# warps_v30.net
KiCad netlist of a schematic drawn in EAGLE
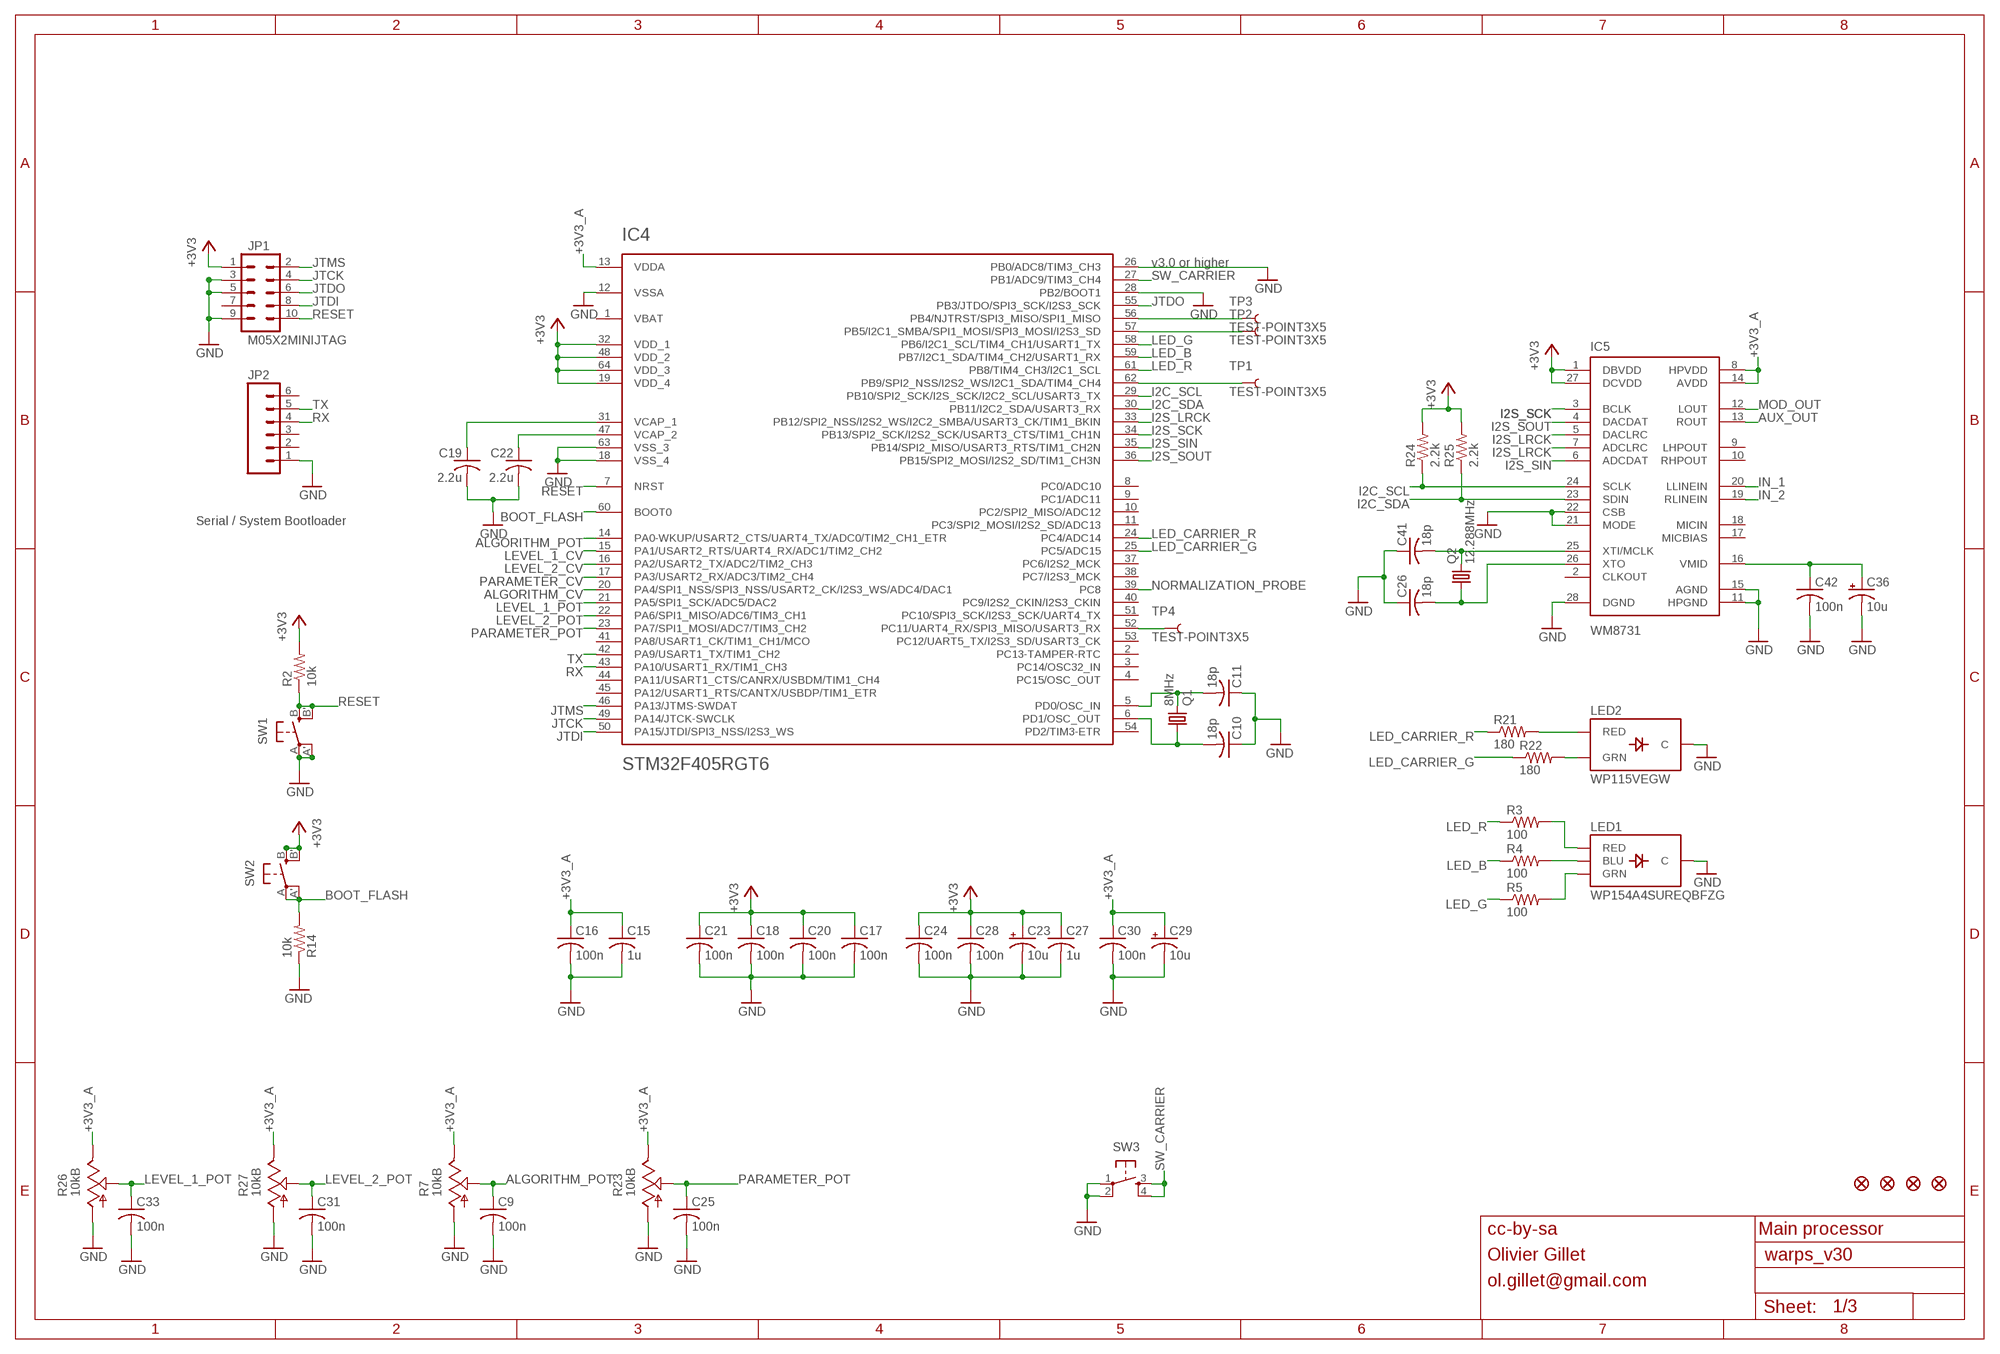
[diagram p0: schematic, sheet 1]
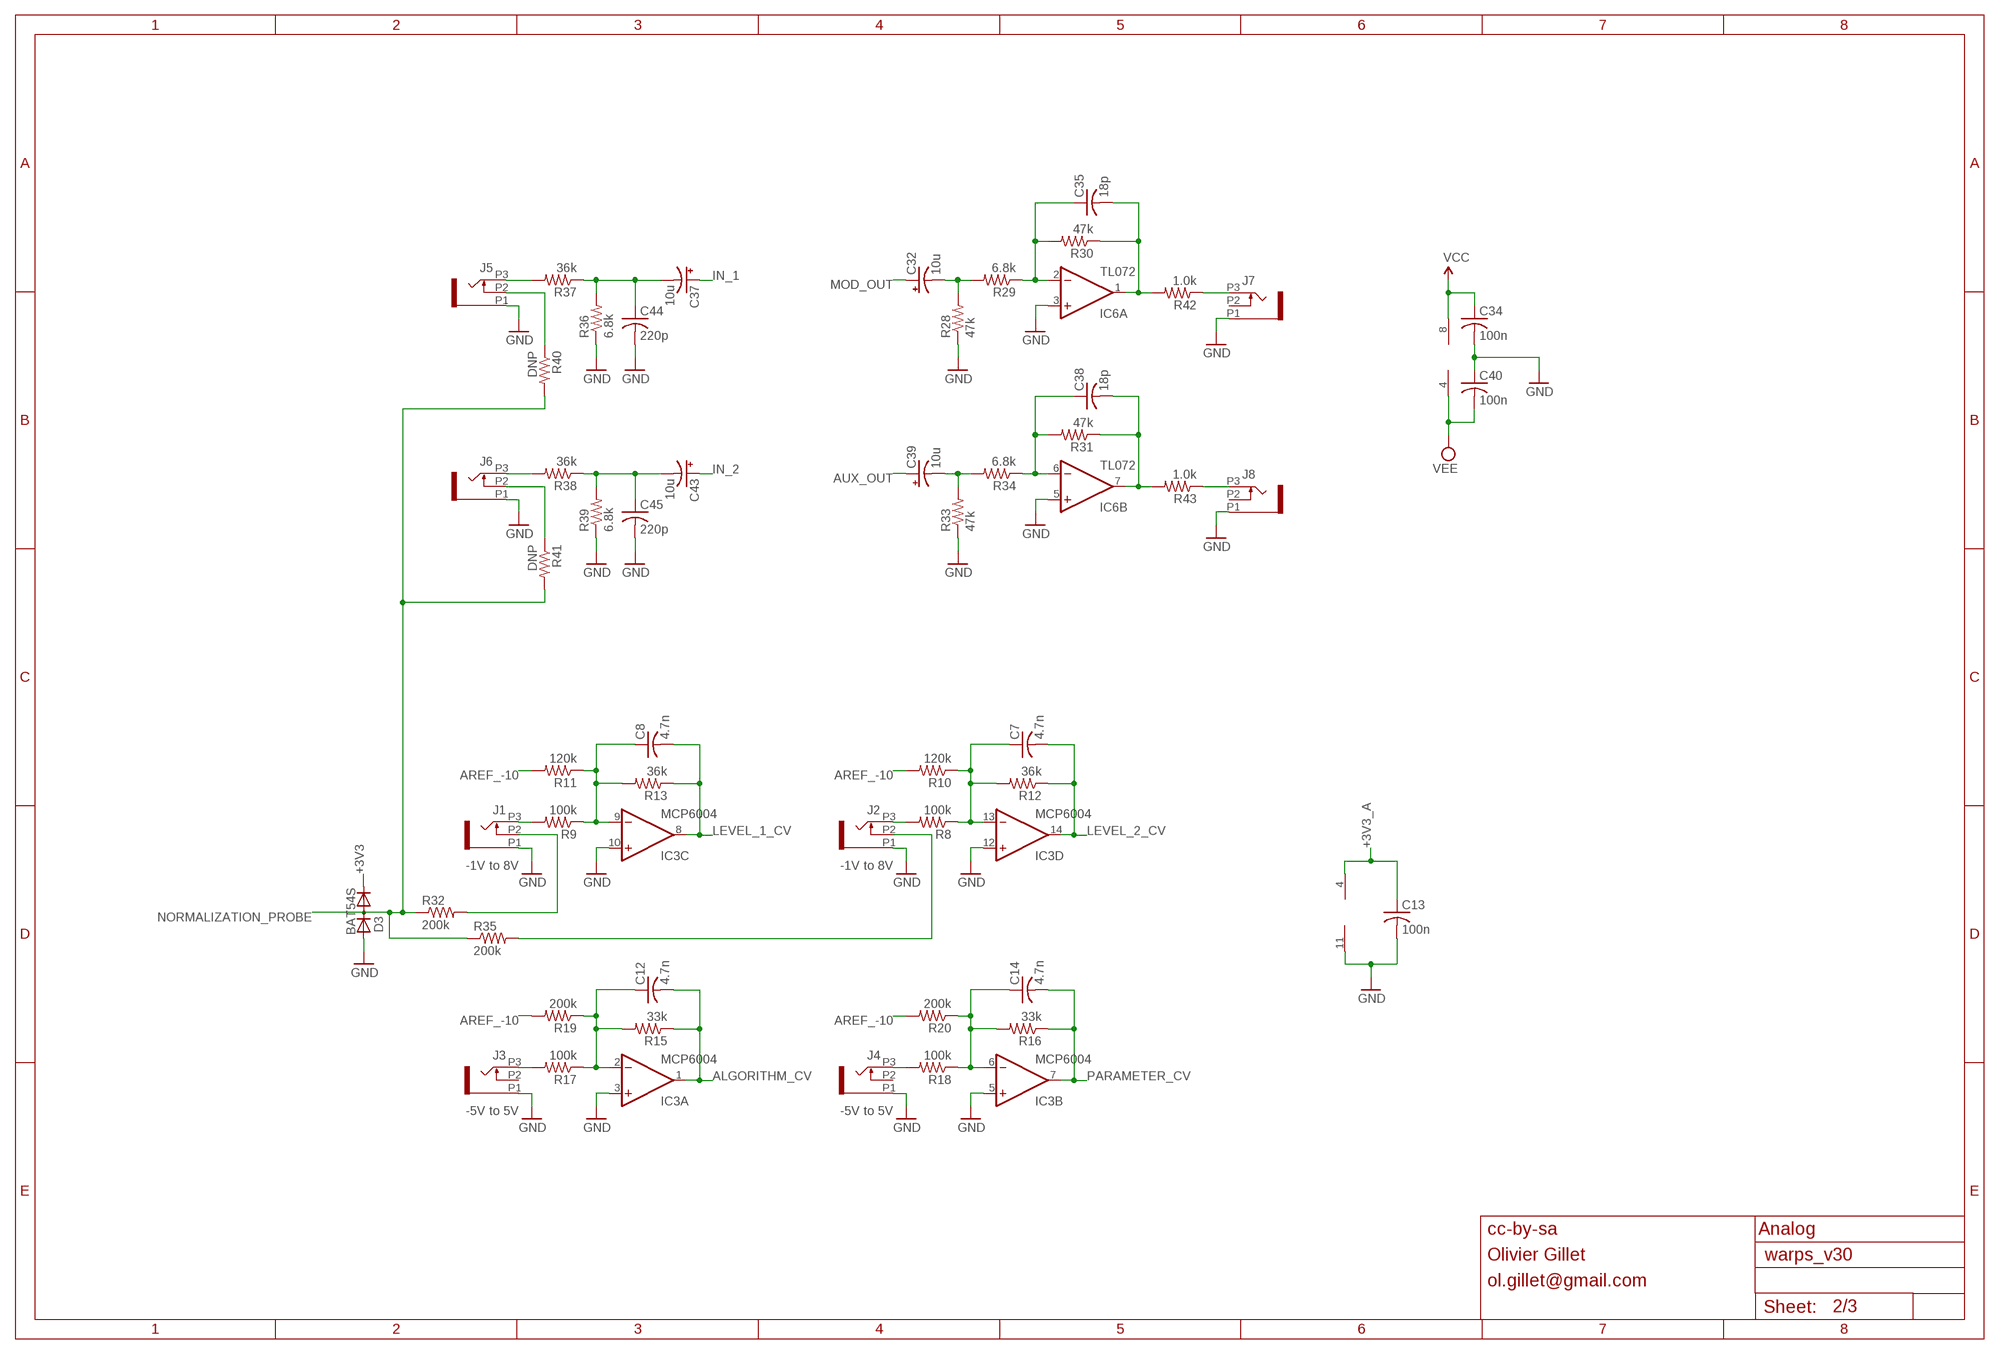
[diagram p1: schematic, sheet 2]
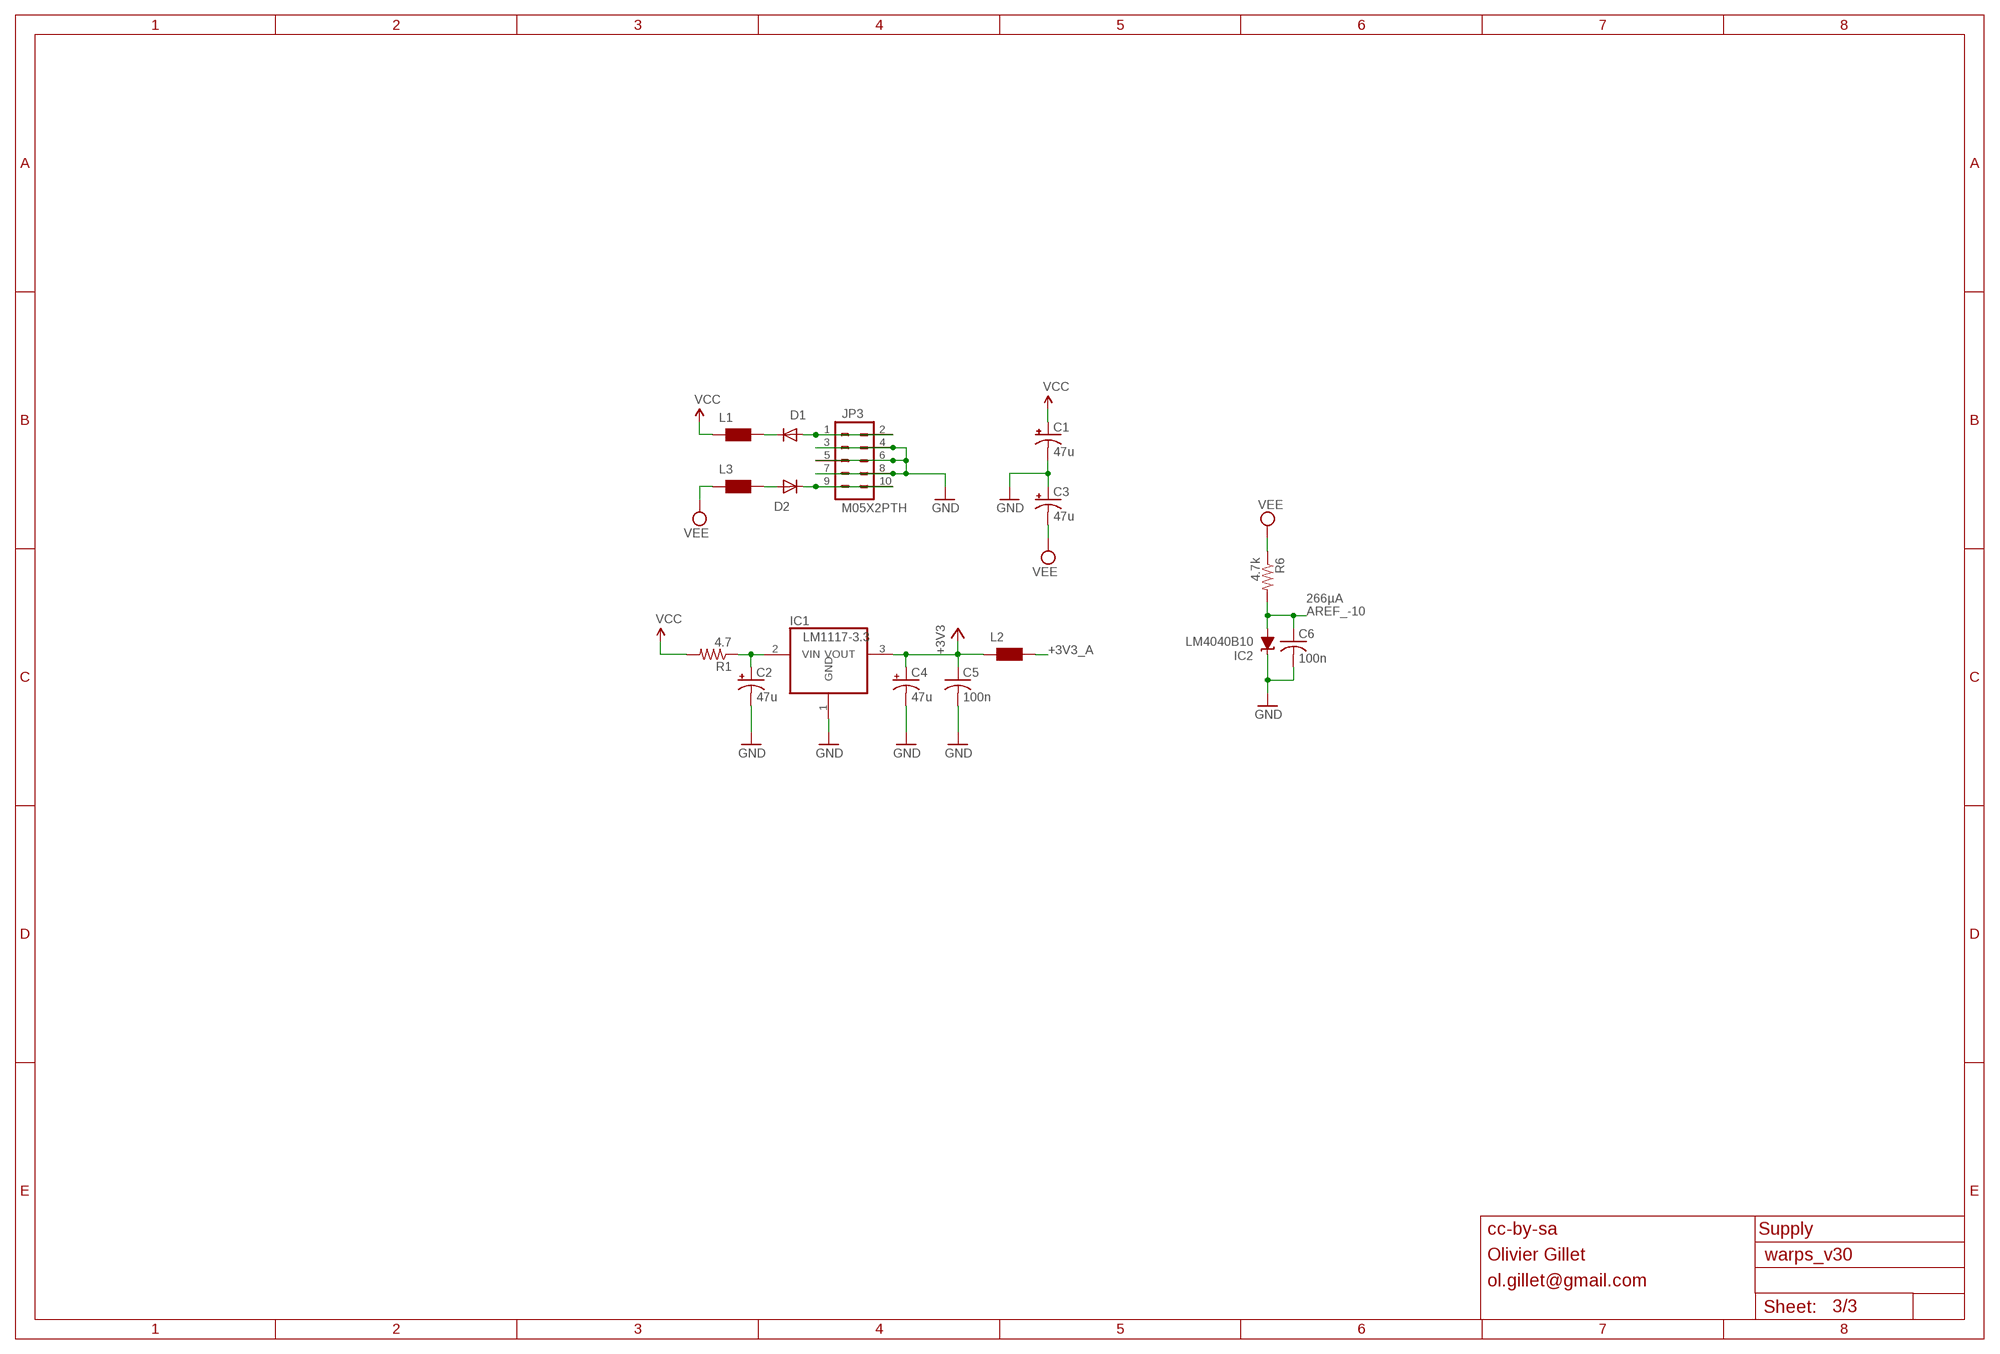
[diagram p2: schematic, sheet 3]

(export (version "E")
  (design (tool "Eeschema 10.0.6"))
  (components
    (comp (ref "C7")
      (value "4.7n")
      (footprint "eagle-import:C0603")
      (libsource (lib "eagle-import") (part "C-USC0603"))
    )
    (comp (ref "C8")
      (value "4.7n")
      (footprint "eagle-import:C0603")
      (libsource (lib "eagle-import") (part "C-USC0603"))
    )
    (comp (ref "C12")
      (value "4.7n")
      (footprint "eagle-import:C0603")
      (libsource (lib "eagle-import") (part "C-USC0603"))
    )
    (comp (ref "C13")
      (value "100n")
      (footprint "eagle-import:C0603")
      (libsource (lib "eagle-import") (part "C-USC0603"))
    )
    (comp (ref "C14")
      (value "4.7n")
      (footprint "eagle-import:C0603")
      (libsource (lib "eagle-import") (part "C-USC0603"))
    )
    (comp (ref "C32")
      (value "10u")
      (footprint "eagle-import:PANASONIC_A")
      (libsource (lib "eagle-import") (part "CPOL-USA"))
    )
    (comp (ref "C34")
      (value "100n")
      (footprint "eagle-import:C0603")
      (libsource (lib "eagle-import") (part "C-USC0603"))
    )
    (comp (ref "C35")
      (value "18p")
      (footprint "eagle-import:C0603")
      (libsource (lib "eagle-import") (part "C-USC0603"))
    )
    (comp (ref "C37")
      (value "10u")
      (footprint "eagle-import:PANASONIC_A")
      (libsource (lib "eagle-import") (part "CPOL-USA"))
    )
    (comp (ref "C38")
      (value "18p")
      (footprint "eagle-import:C0603")
      (libsource (lib "eagle-import") (part "C-USC0603"))
    )
    (comp (ref "C39")
      (value "10u")
      (footprint "eagle-import:PANASONIC_A")
      (libsource (lib "eagle-import") (part "CPOL-USA"))
    )
    (comp (ref "C40")
      (value "100n")
      (footprint "eagle-import:C0603")
      (libsource (lib "eagle-import") (part "C-USC0603"))
    )
    (comp (ref "C43")
      (value "10u")
      (footprint "eagle-import:PANASONIC_A")
      (libsource (lib "eagle-import") (part "CPOL-USA"))
    )
    (comp (ref "C44")
      (value "220p")
      (footprint "eagle-import:C0603")
      (libsource (lib "eagle-import") (part "C-USC0603"))
    )
    (comp (ref "C45")
      (value "220p")
      (footprint "eagle-import:C0603")
      (libsource (lib "eagle-import") (part "C-USC0603"))
    )
    (comp (ref "D3")
      (value "BAT54S")
      (footprint "eagle-import:SOT23")
      (libsource (lib "eagle-import") (part "DIODE_2CACA-SOT23"))
    )
    (comp (ref "IC3")
      (value "MCP6004")
      (footprint "eagle-import:SO14")
      (libsource (lib "eagle-import") (part "TL074D"))
    )
    (comp (ref "IC6")
      (value "TL072")
      (footprint "eagle-import:SO08")
      (libsource (lib "eagle-import") (part "TL072D"))
    )
    (comp (ref "J1")
      (value "PJ301_THONKICONN6")
      (footprint "eagle-import:WQP_PJ_301M6")
      (libsource (lib "eagle-import") (part "PJ301_THONKICONN6"))
    )
    (comp (ref "J2")
      (value "PJ301_THONKICONN6")
      (footprint "eagle-import:WQP_PJ_301M6")
      (libsource (lib "eagle-import") (part "PJ301_THONKICONN6"))
    )
    (comp (ref "J3")
      (value "PJ301_THONKICONN6")
      (footprint "eagle-import:WQP_PJ_301M6")
      (libsource (lib "eagle-import") (part "PJ301_THONKICONN6"))
    )
    (comp (ref "J4")
      (value "PJ301_THONKICONN6")
      (footprint "eagle-import:WQP_PJ_301M6")
      (libsource (lib "eagle-import") (part "PJ301_THONKICONN6"))
    )
    (comp (ref "J5")
      (value "PJ301_THONKICONN6")
      (footprint "eagle-import:WQP_PJ_301M6")
      (libsource (lib "eagle-import") (part "PJ301_THONKICONN6"))
    )
    (comp (ref "J6")
      (value "PJ301_THONKICONN6")
      (footprint "eagle-import:WQP_PJ_301M6")
      (libsource (lib "eagle-import") (part "PJ301_THONKICONN6"))
    )
    (comp (ref "J7")
      (value "PJ301_THONKICONN6")
      (footprint "eagle-import:WQP_PJ_301M6")
      (libsource (lib "eagle-import") (part "PJ301_THONKICONN6"))
    )
    (comp (ref "J8")
      (value "PJ301_THONKICONN6")
      (footprint "eagle-import:WQP_PJ_301M6")
      (libsource (lib "eagle-import") (part "PJ301_THONKICONN6"))
    )
    (comp (ref "R8")
      (value "100k")
      (footprint "eagle-import:R0603")
      (libsource (lib "eagle-import") (part "R-US_R0603"))
    )
    (comp (ref "R9")
      (value "100k")
      (footprint "eagle-import:R0603")
      (libsource (lib "eagle-import") (part "R-US_R0603"))
    )
    (comp (ref "R10")
      (value "120k")
      (footprint "eagle-import:R0603")
      (libsource (lib "eagle-import") (part "R-US_R0603"))
    )
    (comp (ref "R11")
      (value "120k")
      (footprint "eagle-import:R0603")
      (libsource (lib "eagle-import") (part "R-US_R0603"))
    )
    (comp (ref "R12")
      (value "36k")
      (footprint "eagle-import:R0603")
      (libsource (lib "eagle-import") (part "R-US_R0603"))
    )
    (comp (ref "R13")
      (value "36k")
      (footprint "eagle-import:R0603")
      (libsource (lib "eagle-import") (part "R-US_R0603"))
    )
    (comp (ref "R15")
      (value "33k")
      (footprint "eagle-import:R0603")
      (libsource (lib "eagle-import") (part "R-US_R0603"))
    )
    (comp (ref "R16")
      (value "33k")
      (footprint "eagle-import:R0603")
      (libsource (lib "eagle-import") (part "R-US_R0603"))
    )
    (comp (ref "R17")
      (value "100k")
      (footprint "eagle-import:R0603")
      (libsource (lib "eagle-import") (part "R-US_R0603"))
    )
    (comp (ref "R18")
      (value "100k")
      (footprint "eagle-import:R0603")
      (libsource (lib "eagle-import") (part "R-US_R0603"))
    )
    (comp (ref "R19")
      (value "200k")
      (footprint "eagle-import:R0603")
      (libsource (lib "eagle-import") (part "R-US_R0603"))
    )
    (comp (ref "R20")
      (value "200k")
      (footprint "eagle-import:R0603")
      (libsource (lib "eagle-import") (part "R-US_R0603"))
    )
    (comp (ref "R28")
      (value "47k")
      (footprint "eagle-import:R0603")
      (libsource (lib "eagle-import") (part "R-US_R0603"))
    )
    (comp (ref "R29")
      (value "6.8k")
      (footprint "eagle-import:R0603")
      (libsource (lib "eagle-import") (part "R-US_R0603"))
    )
    (comp (ref "R30")
      (value "47k")
      (footprint "eagle-import:R0603")
      (libsource (lib "eagle-import") (part "R-US_R0603"))
    )
    (comp (ref "R31")
      (value "47k")
      (footprint "eagle-import:R0603")
      (libsource (lib "eagle-import") (part "R-US_R0603"))
    )
    (comp (ref "R32")
      (value "200k")
      (footprint "eagle-import:R0603")
      (libsource (lib "eagle-import") (part "R-US_R0603"))
    )
    (comp (ref "R33")
      (value "47k")
      (footprint "eagle-import:R0603")
      (libsource (lib "eagle-import") (part "R-US_R0603"))
    )
    (comp (ref "R34")
      (value "6.8k")
      (footprint "eagle-import:R0603")
      (libsource (lib "eagle-import") (part "R-US_R0603"))
    )
    (comp (ref "R35")
      (value "200k")
      (footprint "eagle-import:R0603")
      (libsource (lib "eagle-import") (part "R-US_R0603"))
    )
    (comp (ref "R36")
      (value "6.8k")
      (footprint "eagle-import:R0603")
      (libsource (lib "eagle-import") (part "R-US_R0603"))
    )
    (comp (ref "R37")
      (value "36k")
      (footprint "eagle-import:R0603")
      (libsource (lib "eagle-import") (part "R-US_R0603"))
    )
    (comp (ref "R38")
      (value "36k")
      (footprint "eagle-import:R0603")
      (libsource (lib "eagle-import") (part "R-US_R0603"))
    )
    (comp (ref "R39")
      (value "6.8k")
      (footprint "eagle-import:R0603")
      (libsource (lib "eagle-import") (part "R-US_R0603"))
    )
    (comp (ref "R40")
      (value "DNP")
      (footprint "eagle-import:R0603")
      (libsource (lib "eagle-import") (part "R-US_R0603"))
    )
    (comp (ref "R41")
      (value "DNP")
      (footprint "eagle-import:R0603")
      (libsource (lib "eagle-import") (part "R-US_R0603"))
    )
    (comp (ref "R42")
      (value "1.0k")
      (footprint "eagle-import:R0603")
      (libsource (lib "eagle-import") (part "R-US_R0603"))
    )
    (comp (ref "R43")
      (value "1.0k")
      (footprint "eagle-import:R0603")
      (libsource (lib "eagle-import") (part "R-US_R0603"))
    )
    (comp (ref "C9")
      (value "100n")
      (footprint "eagle-import:C0603")
      (libsource (lib "eagle-import") (part "C-USC0603"))
    )
    (comp (ref "C10")
      (value "18p")
      (footprint "eagle-import:C0603")
      (libsource (lib "eagle-import") (part "C-USC0603"))
    )
    (comp (ref "C11")
      (value "18p")
      (footprint "eagle-import:C0603")
      (libsource (lib "eagle-import") (part "C-USC0603"))
    )
    (comp (ref "C15")
      (value "1u")
      (footprint "eagle-import:C0603")
      (libsource (lib "eagle-import") (part "C-USC0603"))
    )
    (comp (ref "C16")
      (value "100n")
      (footprint "eagle-import:C0603")
      (libsource (lib "eagle-import") (part "C-USC0603"))
    )
    (comp (ref "C17")
      (value "100n")
      (footprint "eagle-import:C0603")
      (libsource (lib "eagle-import") (part "C-USC0603"))
    )
    (comp (ref "C18")
      (value "100n")
      (footprint "eagle-import:C0603")
      (libsource (lib "eagle-import") (part "C-USC0603"))
    )
    (comp (ref "C19")
      (value "2.2u")
      (footprint "eagle-import:C0805")
      (libsource (lib "eagle-import") (part "C-USC0805"))
    )
    (comp (ref "C20")
      (value "100n")
      (footprint "eagle-import:C0603")
      (libsource (lib "eagle-import") (part "C-USC0603"))
    )
    (comp (ref "C21")
      (value "100n")
      (footprint "eagle-import:C0603")
      (libsource (lib "eagle-import") (part "C-USC0603"))
    )
    (comp (ref "C22")
      (value "2.2u")
      (footprint "eagle-import:C0805")
      (libsource (lib "eagle-import") (part "C-USC0805"))
    )
    (comp (ref "C23")
      (value "10u")
      (footprint "eagle-import:PANASONIC_A")
      (libsource (lib "eagle-import") (part "CPOL-USA"))
    )
    (comp (ref "C24")
      (value "100n")
      (footprint "eagle-import:C0603")
      (libsource (lib "eagle-import") (part "C-USC0603"))
    )
    (comp (ref "C25")
      (value "100n")
      (footprint "eagle-import:C0603")
      (libsource (lib "eagle-import") (part "C-USC0603"))
    )
    (comp (ref "C26")
      (value "18p")
      (footprint "eagle-import:C0603")
      (libsource (lib "eagle-import") (part "C-USC0603"))
    )
    (comp (ref "C27")
      (value "1u")
      (footprint "eagle-import:C0603")
      (libsource (lib "eagle-import") (part "C-USC0603"))
    )
    (comp (ref "C28")
      (value "100n")
      (footprint "eagle-import:C0603")
      (libsource (lib "eagle-import") (part "C-USC0603"))
    )
    (comp (ref "C29")
      (value "10u")
      (footprint "eagle-import:PANASONIC_A")
      (libsource (lib "eagle-import") (part "CPOL-USA"))
    )
    (comp (ref "C30")
      (value "100n")
      (footprint "eagle-import:C0603")
      (libsource (lib "eagle-import") (part "C-USC0603"))
    )
    (comp (ref "C31")
      (value "100n")
      (footprint "eagle-import:C0603")
      (libsource (lib "eagle-import") (part "C-USC0603"))
    )
    (comp (ref "C33")
      (value "100n")
      (footprint "eagle-import:C0603")
      (libsource (lib "eagle-import") (part "C-USC0603"))
    )
    (comp (ref "C36")
      (value "10u")
      (footprint "eagle-import:PANASONIC_A")
      (libsource (lib "eagle-import") (part "CPOL-USA"))
    )
    (comp (ref "C41")
      (value "18p")
      (footprint "eagle-import:C0603")
      (libsource (lib "eagle-import") (part "C-USC0603"))
    )
    (comp (ref "C42")
      (value "100n")
      (footprint "eagle-import:C0603")
      (libsource (lib "eagle-import") (part "C-USC0603"))
    )
    (comp (ref "F1")
      (value "FIDUCIAL1X2")
      (footprint "eagle-import:FIDUCIAL-1X2")
      (libsource (lib "eagle-import") (part "FIDUCIAL1X2"))
    )
    (comp (ref "F2")
      (value "FIDUCIAL1X2")
      (footprint "eagle-import:FIDUCIAL-1X2")
      (libsource (lib "eagle-import") (part "FIDUCIAL1X2"))
    )
    (comp (ref "F3")
      (value "FIDUCIAL1X2")
      (footprint "eagle-import:FIDUCIAL-1X2")
      (libsource (lib "eagle-import") (part "FIDUCIAL1X2"))
    )
    (comp (ref "F4")
      (value "FIDUCIAL1X2")
      (footprint "eagle-import:FIDUCIAL-1X2")
      (libsource (lib "eagle-import") (part "FIDUCIAL1X2"))
    )
    (comp (ref "IC4")
      (value "STM32F405RGT6")
      (footprint "eagle-import:TQFP-10X10-64")
      (libsource (lib "eagle-import") (part "STM32F20X"))
    )
    (comp (ref "IC5")
      (value "WM8731")
      (footprint "eagle-import:SSOP28")
      (libsource (lib "eagle-import") (part "WM8731"))
    )
    (comp (ref "JP1")
      (value "M05X2MINIJTAG")
      (footprint "eagle-import:2X5-1.27")
      (libsource (lib "eagle-import") (part "M05X2MINIJTAG"))
    )
    (comp (ref "JP2")
      (value "M06SIP")
      (footprint "eagle-import:1X06")
      (libsource (lib "eagle-import") (part "M06SIP"))
    )
    (comp (ref "LED1")
      (value "WP154A4SUREQBFZG")
      (footprint "eagle-import:LED-TRICOLOR-THROUGHHOLE")
      (libsource (lib "eagle-import") (part "LED-TRICOLOR-THROUGHHOLE"))
    )
    (comp (ref "LED2")
      (value "WP115VEGW")
      (footprint "eagle-import:LED-BICOLOR-THROUGHHOLE")
      (libsource (lib "eagle-import") (part "LED-BICOLOR-THROUGHHOLE"))
    )
    (comp (ref "Q1")
      (value "8MHz")
      (footprint "eagle-import:HC49UP")
      (libsource (lib "eagle-import") (part "CRYSTALHC49UP"))
    )
    (comp (ref "Q2")
      (value "12.288MHz")
      (footprint "eagle-import:HC49UP")
      (libsource (lib "eagle-import") (part "CRYSTALHC49UP"))
    )
    (comp (ref "R2")
      (value "10k")
      (footprint "eagle-import:R0603")
      (libsource (lib "eagle-import") (part "R-US_R0603"))
    )
    (comp (ref "R3")
      (value "100")
      (footprint "eagle-import:R0603")
      (libsource (lib "eagle-import") (part "R-US_R0603"))
    )
    (comp (ref "R4")
      (value "100")
      (footprint "eagle-import:R0603")
      (libsource (lib "eagle-import") (part "R-US_R0603"))
    )
    (comp (ref "R5")
      (value "100")
      (footprint "eagle-import:R0603")
      (libsource (lib "eagle-import") (part "R-US_R0603"))
    )
    (comp (ref "R7")
      (value "10kB")
      (footprint "eagle-import:ALPS_POT_VERTICAL_PS")
      (libsource (lib "eagle-import") (part "POT_USVERTICAL_PS"))
    )
    (comp (ref "R14")
      (value "10k")
      (footprint "eagle-import:R0603")
      (libsource (lib "eagle-import") (part "R-US_R0603"))
    )
    (comp (ref "R21")
      (value "180")
      (footprint "eagle-import:R0603")
      (libsource (lib "eagle-import") (part "R-US_R0603"))
    )
    (comp (ref "R22")
      (value "180")
      (footprint "eagle-import:R0603")
      (libsource (lib "eagle-import") (part "R-US_R0603"))
    )
    (comp (ref "R23")
      (value "10kB")
      (footprint "eagle-import:ALPS_POT_VERTICAL_PS")
      (libsource (lib "eagle-import") (part "POT_USVERTICAL_PS"))
    )
    (comp (ref "R24")
      (value "2.2k")
      (footprint "eagle-import:R0603")
      (libsource (lib "eagle-import") (part "R-US_R0603"))
    )
    (comp (ref "R25")
      (value "2.2k")
      (footprint "eagle-import:R0603")
      (libsource (lib "eagle-import") (part "R-US_R0603"))
    )
    (comp (ref "R26")
      (value "10kB")
      (footprint "eagle-import:ALPS_POT_VERTICAL")
      (libsource (lib "eagle-import") (part "POT_USVERTICAL"))
    )
    (comp (ref "R27")
      (value "10kB")
      (footprint "eagle-import:ALPS_POT_VERTICAL")
      (libsource (lib "eagle-import") (part "POT_USVERTICAL"))
    )
    (comp (ref "SW1")
      (value "EVQQ2")
      (footprint "eagle-import:EVQ-Q2")
      (libsource (lib "eagle-import") (part "EVQQ2"))
    )
    (comp (ref "SW2")
      (value "EVQQ2")
      (footprint "eagle-import:EVQ-Q2")
      (libsource (lib "eagle-import") (part "EVQQ2"))
    )
    (comp (ref "SW3")
      (value "TAC_SWITCHPTH")
      (footprint "eagle-import:TACTILE-PTH")
      (libsource (lib "eagle-import") (part "TAC_SWITCHPTH"))
    )
    (comp (ref "TP1")
      (value "TEST-POINT3X5")
      (footprint "eagle-import:PAD.03X.05")
      (libsource (lib "eagle-import") (part "TEST-POINT3X5"))
    )
    (comp (ref "TP2")
      (value "TEST-POINT3X5")
      (footprint "eagle-import:PAD.03X.05")
      (libsource (lib "eagle-import") (part "TEST-POINT3X5"))
    )
    (comp (ref "TP3")
      (value "TEST-POINT3X5")
      (footprint "eagle-import:PAD.03X.05")
      (libsource (lib "eagle-import") (part "TEST-POINT3X5"))
    )
    (comp (ref "TP4")
      (value "TEST-POINT3X5")
      (footprint "eagle-import:PAD.03X.05")
      (libsource (lib "eagle-import") (part "TEST-POINT3X5"))
    )
    (comp (ref "C1")
      (value "47u")
      (footprint "eagle-import:PANASONIC_D")
      (libsource (lib "eagle-import") (part "CPOL-USD"))
    )
    (comp (ref "C2")
      (value "47u")
      (footprint "eagle-import:PANASONIC_D")
      (libsource (lib "eagle-import") (part "CPOL-USD"))
    )
    (comp (ref "C3")
      (value "47u")
      (footprint "eagle-import:PANASONIC_D")
      (libsource (lib "eagle-import") (part "CPOL-USD"))
    )
    (comp (ref "C4")
      (value "47u")
      (footprint "eagle-import:PANASONIC_D")
      (libsource (lib "eagle-import") (part "CPOL-USD"))
    )
    (comp (ref "C5")
      (value "100n")
      (footprint "eagle-import:C0603")
      (libsource (lib "eagle-import") (part "C-USC0603"))
    )
    (comp (ref "C6")
      (value "100n")
      (footprint "eagle-import:C0603")
      (libsource (lib "eagle-import") (part "C-USC0603"))
    )
    (comp (ref "D1")
      (value "1N5819HW")
      (footprint "eagle-import:SOD123")
      (libsource (lib "eagle-import") (part "DIODE-SOD123"))
    )
    (comp (ref "D2")
      (value "1N5819HW")
      (footprint "eagle-import:SOD123")
      (libsource (lib "eagle-import") (part "DIODE-SOD123"))
    )
    (comp (ref "IC1")
      (value "LM1117-3.3")
      (footprint "eagle-import:TO252")
      (libsource (lib "eagle-import") (part "REG1117T"))
    )
    (comp (ref "IC2")
      (value "LM4040B10")
      (footprint "eagle-import:DBZ_R-PDSO-G3")
      (libsource (lib "eagle-import") (part "LM4041DBZB12"))
    )
    (comp (ref "JP3")
      (value "M05X2PTH")
      (footprint "eagle-import:AVR_ICSP")
      (libsource (lib "eagle-import") (part "M05X2PTH"))
    )
    (comp (ref "L1")
      (value "WE-CBF_0603")
      (footprint "eagle-import:0603")
      (libsource (lib "eagle-import") (part "WE-CBF_0603"))
    )
    (comp (ref "L2")
      (value "WE-CBF_0603")
      (footprint "eagle-import:0603")
      (libsource (lib "eagle-import") (part "WE-CBF_0603"))
    )
    (comp (ref "L3")
      (value "WE-CBF_0603")
      (footprint "eagle-import:0603")
      (libsource (lib "eagle-import") (part "WE-CBF_0603"))
    )
    (comp (ref "R1")
      (value "4.7")
      (footprint "eagle-import:R1206")
      (libsource (lib "eagle-import") (part "R-US_R1206"))
    )
    (comp (ref "R6")
      (value "4.7k")
      (footprint "eagle-import:R0603")
      (libsource (lib "eagle-import") (part "R-US_R0603"))
    )
  )
  (nets
    (net (code "1") (name "+3V3") (class "Default")
      (node (ref "C17") (pin "1") (pinfunction "1_1") (pintype "passive"))
      (node (ref "C18") (pin "1") (pinfunction "1_1") (pintype "passive"))
      (node (ref "C20") (pin "1") (pinfunction "1_1") (pintype "passive"))
      (node (ref "C21") (pin "1") (pinfunction "1_1") (pintype "passive"))
      (node (ref "C23") (pin "+") (pinfunction "+_+") (pintype "passive"))
      (node (ref "C24") (pin "1") (pinfunction "1_1") (pintype "passive"))
      (node (ref "C27") (pin "1") (pinfunction "1_1") (pintype "passive"))
      (node (ref "C28") (pin "1") (pinfunction "1_1") (pintype "passive"))
      (node (ref "C4") (pin "+") (pinfunction "+_+") (pintype "passive"))
      (node (ref "C5") (pin "1") (pinfunction "1_1") (pintype "passive"))
      (node (ref "D3") (pin "2") (pinfunction "C_2") (pintype "passive"))
      (node (ref "IC1") (pin "3") (pinfunction "VOUT_3") (pintype "output"))
      (node (ref "IC4") (pin "19") (pinfunction "VDD_4_19") (pintype "power_in"))
      (node (ref "IC4") (pin "32") (pinfunction "VDD_1_32") (pintype "power_in"))
      (node (ref "IC4") (pin "48") (pinfunction "VDD_2_48") (pintype "power_in"))
      (node (ref "IC4") (pin "64") (pinfunction "VDD_3_64") (pintype "power_in"))
      (node (ref "IC5") (pin "1") (pinfunction "DBVDD_1") (pintype "bidirectional"))
      (node (ref "IC5") (pin "27") (pinfunction "DCVDD_27") (pintype "bidirectional"))
      (node (ref "JP1") (pin "1") (pinfunction "1_1") (pintype "passive"))
      (node (ref "L2") (pin "1") (pinfunction "1_1") (pintype "passive"))
      (node (ref "R2") (pin "2") (pinfunction "2_2") (pintype "passive"))
      (node (ref "R24") (pin "2") (pinfunction "2_2") (pintype "passive"))
      (node (ref "R25") (pin "2") (pinfunction "2_2") (pintype "passive"))
      (node (ref "SW2") (pin "B") (pinfunction "S_B") (pintype "passive"))
      (node (ref "SW2") (pin "B'") (pinfunction "S1_B'") (pintype "passive"))
    )
    (net (code "2") (name "+3V3_A") (class "Default")
      (node (ref "C13") (pin "1") (pinfunction "1_1") (pintype "passive"))
      (node (ref "C15") (pin "1") (pinfunction "1_1") (pintype "passive"))
      (node (ref "C16") (pin "1") (pinfunction "1_1") (pintype "passive"))
      (node (ref "C29") (pin "+") (pinfunction "+_+") (pintype "passive"))
      (node (ref "C30") (pin "1") (pinfunction "1_1") (pintype "passive"))
      (node (ref "IC3") (pin "4") (pinfunction "V+_4") (pintype "power_in"))
      (node (ref "IC4") (pin "13") (pinfunction "VDDA_13") (pintype "power_in"))
      (node (ref "IC5") (pin "14") (pinfunction "AVDD_14") (pintype "bidirectional"))
      (node (ref "IC5") (pin "8") (pinfunction "HPVDD_8") (pintype "bidirectional"))
      (node (ref "L2") (pin "2") (pinfunction "2_2") (pintype "passive"))
      (node (ref "R23") (pin "P$1") (pinfunction "E_P$1") (pintype "passive"))
      (node (ref "R26") (pin "P$1") (pinfunction "E_P$1") (pintype "passive"))
      (node (ref "R27") (pin "P$1") (pinfunction "E_P$1") (pintype "passive"))
      (node (ref "R7") (pin "P$1") (pinfunction "E_P$1") (pintype "passive"))
    )
    (net (code "3") (name "ALGORITHM_CV") (class "Default")
      (node (ref "C12") (pin "2") (pinfunction "2_2") (pintype "passive"))
      (node (ref "IC3") (pin "1") (pinfunction "OUT_1") (pintype "output"))
      (node (ref "IC4") (pin "20") (pinfunction "PA4/SPI1_NSS/SPI3_NSS/USART2_CK/I2S3_WS/ADC4/DAC1_20") (pintype "bidirectional"))
      (node (ref "R15") (pin "1") (pinfunction "1_1") (pintype "passive"))
    )
    (net (code "4") (name "ALGORITHM_POT") (class "Default")
      (node (ref "C9") (pin "1") (pinfunction "1_1") (pintype "passive"))
      (node (ref "IC4") (pin "14") (pinfunction "PA0-WKUP/USART2_CTS/UART4_TX/ADC0/TIM2_CH1_ETR_14") (pintype "bidirectional"))
      (node (ref "R7") (pin "P$2") (pinfunction "S_P$2") (pintype "passive"))
    )
    (net (code "5") (name "AREF_-10") (class "Default")
      (node (ref "C6") (pin "1") (pinfunction "1_1") (pintype "passive"))
      (node (ref "IC2") (pin "2") (pinfunction "A_2") (pintype "passive"))
      (node (ref "R10") (pin "2") (pinfunction "2_2") (pintype "passive"))
      (node (ref "R11") (pin "2") (pinfunction "2_2") (pintype "passive"))
      (node (ref "R19") (pin "2") (pinfunction "2_2") (pintype "passive"))
      (node (ref "R20") (pin "2") (pinfunction "2_2") (pintype "passive"))
      (node (ref "R6") (pin "2") (pinfunction "2_2") (pintype "passive"))
    )
    (net (code "6") (name "AUX_OUT") (class "Default")
      (node (ref "C39") (pin "+") (pinfunction "+_+") (pintype "passive"))
      (node (ref "IC5") (pin "13") (pinfunction "ROUT_13") (pintype "bidirectional"))
    )
    (net (code "7") (name "BOOT_FLASH") (class "Default")
      (node (ref "IC4") (pin "60") (pinfunction "BOOT0_60") (pintype "bidirectional"))
      (node (ref "R14") (pin "2") (pinfunction "2_2") (pintype "passive"))
      (node (ref "SW2") (pin "A") (pinfunction "P_A") (pintype "passive"))
      (node (ref "SW2") (pin "A'") (pinfunction "P1_A'") (pintype "passive"))
    )
    (net (code "8") (name "GND") (class "Default")
      (node (ref "C1") (pin "-") (pinfunction "-_-") (pintype "passive"))
      (node (ref "C10") (pin "1") (pinfunction "1_1") (pintype "passive"))
      (node (ref "C11") (pin "1") (pinfunction "1_1") (pintype "passive"))
      (node (ref "C13") (pin "2") (pinfunction "2_2") (pintype "passive"))
      (node (ref "C15") (pin "2") (pinfunction "2_2") (pintype "passive"))
      (node (ref "C16") (pin "2") (pinfunction "2_2") (pintype "passive"))
      (node (ref "C17") (pin "2") (pinfunction "2_2") (pintype "passive"))
      (node (ref "C18") (pin "2") (pinfunction "2_2") (pintype "passive"))
      (node (ref "C19") (pin "2") (pinfunction "2_2") (pintype "passive"))
      (node (ref "C2") (pin "-") (pinfunction "-_-") (pintype "passive"))
      (node (ref "C20") (pin "2") (pinfunction "2_2") (pintype "passive"))
      (node (ref "C21") (pin "2") (pinfunction "2_2") (pintype "passive"))
      (node (ref "C22") (pin "2") (pinfunction "2_2") (pintype "passive"))
      (node (ref "C23") (pin "-") (pinfunction "-_-") (pintype "passive"))
      (node (ref "C24") (pin "2") (pinfunction "2_2") (pintype "passive"))
      (node (ref "C25") (pin "2") (pinfunction "2_2") (pintype "passive"))
      (node (ref "C26") (pin "1") (pinfunction "1_1") (pintype "passive"))
      (node (ref "C27") (pin "2") (pinfunction "2_2") (pintype "passive"))
      (node (ref "C28") (pin "2") (pinfunction "2_2") (pintype "passive"))
      (node (ref "C29") (pin "-") (pinfunction "-_-") (pintype "passive"))
      (node (ref "C3") (pin "+") (pinfunction "+_+") (pintype "passive"))
      (node (ref "C30") (pin "2") (pinfunction "2_2") (pintype "passive"))
      (node (ref "C31") (pin "2") (pinfunction "2_2") (pintype "passive"))
      (node (ref "C33") (pin "2") (pinfunction "2_2") (pintype "passive"))
      (node (ref "C34") (pin "2") (pinfunction "2_2") (pintype "passive"))
      (node (ref "C36") (pin "-") (pinfunction "-_-") (pintype "passive"))
      (node (ref "C4") (pin "-") (pinfunction "-_-") (pintype "passive"))
      (node (ref "C40") (pin "1") (pinfunction "1_1") (pintype "passive"))
      (node (ref "C41") (pin "1") (pinfunction "1_1") (pintype "passive"))
      (node (ref "C42") (pin "2") (pinfunction "2_2") (pintype "passive"))
      (node (ref "C44") (pin "2") (pinfunction "2_2") (pintype "passive"))
      (node (ref "C45") (pin "2") (pinfunction "2_2") (pintype "passive"))
      (node (ref "C5") (pin "2") (pinfunction "2_2") (pintype "passive"))
      (node (ref "C6") (pin "2") (pinfunction "2_2") (pintype "passive"))
      (node (ref "C9") (pin "2") (pinfunction "2_2") (pintype "passive"))
      (node (ref "D3") (pin "1") (pinfunction "A_1") (pintype "passive"))
      (node (ref "IC1") (pin "1") (pinfunction "GND_1") (pintype "power_in"))
      (node (ref "IC2") (pin "1") (pinfunction "C_1") (pintype "passive"))
      (node (ref "IC3") (pin "10") (pinfunction "+IN_10") (pintype "input"))
      (node (ref "IC3") (pin "11") (pinfunction "V-_11") (pintype "power_in"))
      (node (ref "IC3") (pin "12") (pinfunction "+IN_12") (pintype "input"))
      (node (ref "IC3") (pin "3") (pinfunction "+IN_3") (pintype "input"))
      (node (ref "IC3") (pin "5") (pinfunction "+IN_5") (pintype "input"))
      (node (ref "IC4") (pin "12") (pinfunction "VSSA_12") (pintype "power_in"))
      (node (ref "IC4") (pin "18") (pinfunction "VSS_4_18") (pintype "power_in"))
      (node (ref "IC4") (pin "26") (pinfunction "PB0/ADC8/TIM3_CH3_26") (pintype "bidirectional"))
      (node (ref "IC4") (pin "28") (pinfunction "PB2/BOOT1_28") (pintype "bidirectional"))
      (node (ref "IC4") (pin "63") (pinfunction "VSS_3_63") (pintype "power_in"))
      (node (ref "IC5") (pin "11") (pinfunction "HPGND_11") (pintype "bidirectional"))
      (node (ref "IC5") (pin "15") (pinfunction "AGND_15") (pintype "bidirectional"))
      (node (ref "IC5") (pin "21") (pinfunction "MODE_21") (pintype "bidirectional"))
      (node (ref "IC5") (pin "22") (pinfunction "CSB_22") (pintype "bidirectional"))
      (node (ref "IC5") (pin "28") (pinfunction "DGND_28") (pintype "bidirectional"))
      (node (ref "IC6") (pin "3") (pinfunction "+IN_3") (pintype "input"))
      (node (ref "IC6") (pin "5") (pinfunction "+IN_5") (pintype "input"))
      (node (ref "J1") (pin "P1") (pinfunction "1_P1") (pintype "passive"))
      (node (ref "J2") (pin "P1") (pinfunction "1_P1") (pintype "passive"))
      (node (ref "J3") (pin "P1") (pinfunction "1_P1") (pintype "passive"))
      (node (ref "J4") (pin "P1") (pinfunction "1_P1") (pintype "passive"))
      (node (ref "J5") (pin "P1") (pinfunction "1_P1") (pintype "passive"))
      (node (ref "J6") (pin "P1") (pinfunction "1_P1") (pintype "passive"))
      (node (ref "J7") (pin "P1") (pinfunction "1_P1") (pintype "passive"))
      (node (ref "J8") (pin "P1") (pinfunction "1_P1") (pintype "passive"))
      (node (ref "JP1") (pin "3") (pinfunction "3_3") (pintype "passive"))
      (node (ref "JP1") (pin "5") (pinfunction "5_5") (pintype "passive"))
      (node (ref "JP1") (pin "9") (pinfunction "9_9") (pintype "passive"))
      (node (ref "JP2") (pin "1") (pinfunction "1_1") (pintype "passive"))
      (node (ref "JP3") (pin "3") (pinfunction "3_3") (pintype "passive"))
      (node (ref "JP3") (pin "4") (pinfunction "4_4") (pintype "passive"))
      (node (ref "JP3") (pin "5") (pinfunction "5_5") (pintype "passive"))
      (node (ref "JP3") (pin "6") (pinfunction "6_6") (pintype "passive"))
      (node (ref "JP3") (pin "7") (pinfunction "7_7") (pintype "passive"))
      (node (ref "JP3") (pin "8") (pinfunction "8_8") (pintype "passive"))
      (node (ref "LED1") (pin "GND") (pinfunction "C_GND") (pintype "bidirectional"))
      (node (ref "LED2") (pin "2") (pinfunction "C_2") (pintype "bidirectional"))
      (node (ref "R14") (pin "1") (pinfunction "1_1") (pintype "passive"))
      (node (ref "R23") (pin "P$3") (pinfunction "A_P$3") (pintype "passive"))
      (node (ref "R26") (pin "P$3") (pinfunction "A_P$3") (pintype "passive"))
      (node (ref "R27") (pin "P$3") (pinfunction "A_P$3") (pintype "passive"))
      (node (ref "R28") (pin "1") (pinfunction "1_1") (pintype "passive"))
      (node (ref "R33") (pin "1") (pinfunction "1_1") (pintype "passive"))
      (node (ref "R36") (pin "1") (pinfunction "1_1") (pintype "passive"))
      (node (ref "R39") (pin "1") (pinfunction "1_1") (pintype "passive"))
      (node (ref "R7") (pin "P$3") (pinfunction "A_P$3") (pintype "passive"))
      (node (ref "SW1") (pin "A") (pinfunction "P_A") (pintype "passive"))
      (node (ref "SW1") (pin "A'") (pinfunction "P1_A'") (pintype "passive"))
      (node (ref "SW3") (pin "1") (pinfunction "1_1") (pintype "passive"))
      (node (ref "SW3") (pin "2") (pinfunction "2_2") (pintype "passive"))
    )
    (net (code "9") (name "I2C_SCL") (class "Default")
      (node (ref "IC4") (pin "29") (pinfunction "PB10/SPI2_SCK/I2S_SCK/I2C2_SCL/USART3_TX_29") (pintype "bidirectional"))
      (node (ref "IC5") (pin "24") (pinfunction "SCLK_24") (pintype "bidirectional"))
      (node (ref "R24") (pin "1") (pinfunction "1_1") (pintype "passive"))
    )
    (net (code "10") (name "I2C_SDA") (class "Default")
      (node (ref "IC4") (pin "30") (pinfunction "PB11/I2C2_SDA/USART3_RX_30") (pintype "bidirectional"))
      (node (ref "IC5") (pin "23") (pinfunction "SDIN_23") (pintype "bidirectional"))
      (node (ref "R25") (pin "1") (pinfunction "1_1") (pintype "passive"))
    )
    (net (code "11") (name "I2S_LRCK") (class "Default")
      (node (ref "IC4") (pin "33") (pinfunction "PB12/SPI2_NSS/I2S2_WS/I2C2_SMBA/USART3_CK/TIM1_BKIN_33") (pintype "bidirectional"))
      (node (ref "IC5") (pin "5") (pinfunction "DACLRC_5") (pintype "bidirectional"))
      (node (ref "IC5") (pin "7") (pinfunction "ADCLRC_7") (pintype "bidirectional"))
    )
    (net (code "12") (name "I2S_SCK") (class "Default")
      (node (ref "IC4") (pin "34") (pinfunction "PB13/SPI2_SCK/I2S2_SCK/USART3_CTS/TIM1_CH1N_34") (pintype "bidirectional"))
      (node (ref "IC5") (pin "3") (pinfunction "BCLK_3") (pintype "bidirectional"))
    )
    (net (code "13") (name "I2S_SIN") (class "Default")
      (node (ref "IC4") (pin "35") (pinfunction "PB14/SPI2_MISO/USART3_RTS/TIM1_CH2N_35") (pintype "bidirectional"))
      (node (ref "IC5") (pin "6") (pinfunction "ADCDAT_6") (pintype "bidirectional"))
    )
    (net (code "14") (name "I2S_SOUT") (class "Default")
      (node (ref "IC4") (pin "36") (pinfunction "PB15/SPI2_MOSI/I2S2_SD/TIM1_CH3N_36") (pintype "bidirectional"))
      (node (ref "IC5") (pin "4") (pinfunction "DACDAT_4") (pintype "bidirectional"))
    )
    (net (code "15") (name "IN_1") (class "Default")
      (node (ref "C37") (pin "+") (pinfunction "+_+") (pintype "passive"))
      (node (ref "IC5") (pin "20") (pinfunction "LLINEIN_20") (pintype "bidirectional"))
    )
    (net (code "16") (name "IN_2") (class "Default")
      (node (ref "C43") (pin "+") (pinfunction "+_+") (pintype "passive"))
      (node (ref "IC5") (pin "19") (pinfunction "RLINEIN_19") (pintype "bidirectional"))
    )
    (net (code "17") (name "JTCK") (class "Default")
      (node (ref "IC4") (pin "49") (pinfunction "PA14/JTCK-SWCLK_49") (pintype "bidirectional"))
      (node (ref "JP1") (pin "4") (pinfunction "4_4") (pintype "passive"))
    )
    (net (code "18") (name "JTDI") (class "Default")
      (node (ref "IC4") (pin "50") (pinfunction "PA15/JTDI/SPI3_NSS/I2S3_WS_50") (pintype "bidirectional"))
      (node (ref "JP1") (pin "8") (pinfunction "8_8") (pintype "passive"))
    )
    (net (code "19") (name "JTDO") (class "Default")
      (node (ref "IC4") (pin "55") (pinfunction "PB3/JTDO/SPI3_SCK/I2S3_SCK_55") (pintype "bidirectional"))
      (node (ref "JP1") (pin "6") (pinfunction "6_6") (pintype "passive"))
    )
    (net (code "20") (name "JTMS") (class "Default")
      (node (ref "IC4") (pin "46") (pinfunction "PA13/JTMS-SWDAT_46") (pintype "bidirectional"))
      (node (ref "JP1") (pin "2") (pinfunction "2_2") (pintype "passive"))
    )
    (net (code "21") (name "LED_B") (class "Default")
      (node (ref "IC4") (pin "59") (pinfunction "PB7/I2C1_SDA/TIM4_CH2/USART1_RX_59") (pintype "bidirectional"))
      (node (ref "R4") (pin "1") (pinfunction "1_1") (pintype "passive"))
    )
    (net (code "22") (name "LED_CARRIER_G") (class "Default")
      (node (ref "IC4") (pin "25") (pinfunction "PC5/ADC15_25") (pintype "bidirectional"))
      (node (ref "R22") (pin "1") (pinfunction "1_1") (pintype "passive"))
    )
    (net (code "23") (name "LED_CARRIER_R") (class "Default")
      (node (ref "IC4") (pin "24") (pinfunction "PC4/ADC14_24") (pintype "bidirectional"))
      (node (ref "R21") (pin "1") (pinfunction "1_1") (pintype "passive"))
    )
    (net (code "24") (name "LED_G") (class "Default")
      (node (ref "IC4") (pin "58") (pinfunction "PB6/I2C1_SCL/TIM4_CH1/USART1_TX_58") (pintype "bidirectional"))
      (node (ref "R5") (pin "1") (pinfunction "1_1") (pintype "passive"))
    )
    (net (code "25") (name "LED_R") (class "Default")
      (node (ref "IC4") (pin "61") (pinfunction "PB8/TIM4_CH3/I2C1_SCL_61") (pintype "bidirectional"))
      (node (ref "R3") (pin "1") (pinfunction "1_1") (pintype "passive"))
    )
    (net (code "26") (name "LEVEL_1_CV") (class "Default")
      (node (ref "C8") (pin "2") (pinfunction "2_2") (pintype "passive"))
      (node (ref "IC3") (pin "8") (pinfunction "OUT_8") (pintype "output"))
      (node (ref "IC4") (pin "15") (pinfunction "PA1/USART2_RTS/UART4_RX/ADC1/TIM2_CH2_15") (pintype "bidirectional"))
      (node (ref "R13") (pin "1") (pinfunction "1_1") (pintype "passive"))
    )
    (net (code "27") (name "LEVEL_1_POT") (class "Default")
      (node (ref "C33") (pin "1") (pinfunction "1_1") (pintype "passive"))
      (node (ref "IC4") (pin "21") (pinfunction "PA5/SPI1_SCK/ADC5/DAC2_21") (pintype "bidirectional"))
      (node (ref "R26") (pin "P$2") (pinfunction "S_P$2") (pintype "passive"))
    )
    (net (code "28") (name "LEVEL_2_CV") (class "Default")
      (node (ref "C7") (pin "2") (pinfunction "2_2") (pintype "passive"))
      (node (ref "IC3") (pin "14") (pinfunction "OUT_14") (pintype "output"))
      (node (ref "IC4") (pin "16") (pinfunction "PA2/USART2_TX/ADC2/TIM2_CH3_16") (pintype "bidirectional"))
      (node (ref "R12") (pin "1") (pinfunction "1_1") (pintype "passive"))
    )
    (net (code "29") (name "LEVEL_2_POT") (class "Default")
      (node (ref "C31") (pin "1") (pinfunction "1_1") (pintype "passive"))
      (node (ref "IC4") (pin "22") (pinfunction "PA6/SPI1_MISO/ADC6/TIM3_CH1_22") (pintype "bidirectional"))
      (node (ref "R27") (pin "P$2") (pinfunction "S_P$2") (pintype "passive"))
    )
    (net (code "30") (name "MOD_OUT") (class "Default")
      (node (ref "C32") (pin "+") (pinfunction "+_+") (pintype "passive"))
      (node (ref "IC5") (pin "12") (pinfunction "LOUT_12") (pintype "bidirectional"))
    )
    (net (code "31") (name "NORMALIZATION_PROBE") (class "Default")
      (node (ref "D3") (pin "3") (pinfunction "AC_3") (pintype "passive"))
      (node (ref "IC4") (pin "39") (pinfunction "PC8_39") (pintype "bidirectional"))
      (node (ref "R32") (pin "1") (pinfunction "1_1") (pintype "passive"))
      (node (ref "R35") (pin "1") (pinfunction "1_1") (pintype "passive"))
      (node (ref "R40") (pin "2") (pinfunction "2_2") (pintype "passive"))
      (node (ref "R41") (pin "2") (pinfunction "2_2") (pintype "passive"))
    )
    (net (code "32") (name "Net-(C32-Pad-)") (class "Default")
      (node (ref "C32") (pin "-") (pinfunction "-_-") (pintype "passive"))
      (node (ref "R28") (pin "2") (pinfunction "2_2") (pintype "passive"))
      (node (ref "R29") (pin "2") (pinfunction "2_2") (pintype "passive"))
    )
    (net (code "33") (name "Net-(C37-Pad-)") (class "Default")
      (node (ref "C37") (pin "-") (pinfunction "-_-") (pintype "passive"))
      (node (ref "C44") (pin "1") (pinfunction "1_1") (pintype "passive"))
      (node (ref "R36") (pin "2") (pinfunction "2_2") (pintype "passive"))
      (node (ref "R37") (pin "1") (pinfunction "1_1") (pintype "passive"))
    )
    (net (code "34") (name "Net-(C39-Pad-)") (class "Default")
      (node (ref "C39") (pin "-") (pinfunction "-_-") (pintype "passive"))
      (node (ref "R33") (pin "2") (pinfunction "2_2") (pintype "passive"))
      (node (ref "R34") (pin "2") (pinfunction "2_2") (pintype "passive"))
    )
    (net (code "35") (name "Net-(C43-Pad-)") (class "Default")
      (node (ref "C43") (pin "-") (pinfunction "-_-") (pintype "passive"))
      (node (ref "C45") (pin "1") (pinfunction "1_1") (pintype "passive"))
      (node (ref "R38") (pin "1") (pinfunction "1_1") (pintype "passive"))
      (node (ref "R39") (pin "2") (pinfunction "2_2") (pintype "passive"))
    )
    (net (code "36") (name "Net-(D1-PadA)") (class "Default")
      (node (ref "D1") (pin "A") (pinfunction "A_A") (pintype "passive"))
      (node (ref "JP3") (pin "1") (pinfunction "1_1") (pintype "passive"))
      (node (ref "JP3") (pin "2") (pinfunction "2_2") (pintype "passive"))
    )
    (net (code "37") (name "Net-(D1-PadC)") (class "Default")
      (node (ref "D1") (pin "C") (pinfunction "C_C") (pintype "passive"))
      (node (ref "L1") (pin "2") (pinfunction "2_2") (pintype "passive"))
    )
    (net (code "38") (name "Net-(D2-PadA)") (class "Default")
      (node (ref "D2") (pin "A") (pinfunction "A_A") (pintype "passive"))
      (node (ref "L3") (pin "2") (pinfunction "2_2") (pintype "passive"))
    )
    (net (code "39") (name "Net-(D2-PadC)") (class "Default")
      (node (ref "D2") (pin "C") (pinfunction "C_C") (pintype "passive"))
      (node (ref "JP3") (pin "10") (pinfunction "10_10") (pintype "passive"))
      (node (ref "JP3") (pin "9") (pinfunction "9_9") (pintype "passive"))
    )
    (net (code "40") (name "Net-(IC1-VIN)") (class "Default")
      (node (ref "C2") (pin "+") (pinfunction "+_+") (pintype "passive"))
      (node (ref "IC1") (pin "2") (pinfunction "VIN_2") (pintype "input"))
      (node (ref "R1") (pin "1") (pinfunction "1_1") (pintype "passive"))
    )
    (net (code "41") (name "Net-(IC3A--IN)") (class "Default")
      (node (ref "C12") (pin "1") (pinfunction "1_1") (pintype "passive"))
      (node (ref "IC3") (pin "2") (pinfunction "-IN_2") (pintype "input"))
      (node (ref "R15") (pin "2") (pinfunction "2_2") (pintype "passive"))
      (node (ref "R17") (pin "1") (pinfunction "1_1") (pintype "passive"))
      (node (ref "R19") (pin "1") (pinfunction "1_1") (pintype "passive"))
    )
    (net (code "42") (name "Net-(IC3B--IN)") (class "Default")
      (node (ref "C14") (pin "1") (pinfunction "1_1") (pintype "passive"))
      (node (ref "IC3") (pin "6") (pinfunction "-IN_6") (pintype "input"))
      (node (ref "R16") (pin "2") (pinfunction "2_2") (pintype "passive"))
      (node (ref "R18") (pin "1") (pinfunction "1_1") (pintype "passive"))
      (node (ref "R20") (pin "1") (pinfunction "1_1") (pintype "passive"))
    )
    (net (code "43") (name "Net-(IC3C--IN)") (class "Default")
      (node (ref "C8") (pin "1") (pinfunction "1_1") (pintype "passive"))
      (node (ref "IC3") (pin "9") (pinfunction "-IN_9") (pintype "input"))
      (node (ref "R11") (pin "1") (pinfunction "1_1") (pintype "passive"))
      (node (ref "R13") (pin "2") (pinfunction "2_2") (pintype "passive"))
      (node (ref "R9") (pin "1") (pinfunction "1_1") (pintype "passive"))
    )
    (net (code "44") (name "Net-(IC3D--IN)") (class "Default")
      (node (ref "C7") (pin "1") (pinfunction "1_1") (pintype "passive"))
      (node (ref "IC3") (pin "13") (pinfunction "-IN_13") (pintype "input"))
      (node (ref "R10") (pin "1") (pinfunction "1_1") (pintype "passive"))
      (node (ref "R12") (pin "2") (pinfunction "2_2") (pintype "passive"))
      (node (ref "R8") (pin "1") (pinfunction "1_1") (pintype "passive"))
    )
    (net (code "45") (name "Net-(IC4-PB4{slash}NJTRST{slash}SPI3_MISO{slash}SPI1_MISO)") (class "Default")
      (node (ref "IC4") (pin "56") (pinfunction "PB4/NJTRST/SPI3_MISO/SPI1_MISO_56") (pintype "bidirectional"))
      (node (ref "TP3") (pin "P$1") (pinfunction "1_P$1") (pintype "bidirectional"))
    )
    (net (code "46") (name "Net-(IC4-PB5{slash}I2C1_SMBA{slash}SPI1_MOSI{slash}SPI3_MOSI{slash}I2S3_SD)") (class "Default")
      (node (ref "IC4") (pin "57") (pinfunction "PB5/I2C1_SMBA/SPI1_MOSI/SPI3_MOSI/I2S3_SD_57") (pintype "bidirectional"))
      (node (ref "TP2") (pin "P$1") (pinfunction "1_P$1") (pintype "bidirectional"))
    )
    (net (code "47") (name "Net-(IC4-PB9{slash}SPI2_NSS{slash}I2S2_WS{slash}I2C1_SDA{slash}TIM4_CH4)") (class "Default")
      (node (ref "IC4") (pin "62") (pinfunction "PB9/SPI2_NSS/I2S2_WS/I2C1_SDA/TIM4_CH4_62") (pintype "bidirectional"))
      (node (ref "TP1") (pin "P$1") (pinfunction "1_P$1") (pintype "bidirectional"))
    )
    (net (code "48") (name "Net-(IC4-PC11{slash}UART4_RX{slash}SPI3_MISO{slash}USART3_RX)") (class "Default")
      (node (ref "IC4") (pin "52") (pinfunction "PC11/UART4_RX/SPI3_MISO/USART3_RX_52") (pintype "bidirectional"))
      (node (ref "TP4") (pin "P$1") (pinfunction "1_P$1") (pintype "bidirectional"))
    )
    (net (code "49") (name "Net-(IC4-PD0{slash}OSC_IN)") (class "Default")
      (node (ref "C11") (pin "2") (pinfunction "2_2") (pintype "passive"))
      (node (ref "IC4") (pin "5") (pinfunction "PD0/OSC_IN_5") (pintype "bidirectional"))
      (node (ref "Q1") (pin "2") (pinfunction "2_2") (pintype "passive"))
    )
    (net (code "50") (name "Net-(IC4-PD1{slash}OSC_OUT)") (class "Default")
      (node (ref "C10") (pin "2") (pinfunction "2_2") (pintype "passive"))
      (node (ref "IC4") (pin "6") (pinfunction "PD1/OSC_OUT_6") (pintype "bidirectional"))
      (node (ref "Q1") (pin "1") (pinfunction "1_1") (pintype "passive"))
    )
    (net (code "51") (name "Net-(IC4-VCAP_1)") (class "Default")
      (node (ref "C19") (pin "1") (pinfunction "1_1") (pintype "passive"))
      (node (ref "IC4") (pin "31") (pinfunction "VCAP_1_31") (pintype "power_in"))
    )
    (net (code "52") (name "Net-(IC4-VCAP_2)") (class "Default")
      (node (ref "C22") (pin "1") (pinfunction "1_1") (pintype "passive"))
      (node (ref "IC4") (pin "47") (pinfunction "VCAP_2_47") (pintype "power_in"))
    )
    (net (code "53") (name "Net-(IC5-VMID)") (class "Default")
      (node (ref "C36") (pin "+") (pinfunction "+_+") (pintype "passive"))
      (node (ref "C42") (pin "1") (pinfunction "1_1") (pintype "passive"))
      (node (ref "IC5") (pin "16") (pinfunction "VMID_16") (pintype "bidirectional"))
    )
    (net (code "54") (name "Net-(IC5-XTI{slash}MCLK)") (class "Default")
      (node (ref "C41") (pin "2") (pinfunction "2_2") (pintype "passive"))
      (node (ref "IC5") (pin "25") (pinfunction "XTI/MCLK_25") (pintype "bidirectional"))
      (node (ref "Q2") (pin "2") (pinfunction "2_2") (pintype "passive"))
    )
    (net (code "55") (name "Net-(IC5-XTO)") (class "Default")
      (node (ref "C26") (pin "2") (pinfunction "2_2") (pintype "passive"))
      (node (ref "IC5") (pin "26") (pinfunction "XTO_26") (pintype "bidirectional"))
      (node (ref "Q2") (pin "1") (pinfunction "1_1") (pintype "passive"))
    )
    (net (code "56") (name "Net-(IC6A--IN)") (class "Default")
      (node (ref "C35") (pin "1") (pinfunction "1_1") (pintype "passive"))
      (node (ref "IC6") (pin "2") (pinfunction "-IN_2") (pintype "input"))
      (node (ref "R29") (pin "1") (pinfunction "1_1") (pintype "passive"))
      (node (ref "R30") (pin "2") (pinfunction "2_2") (pintype "passive"))
    )
    (net (code "57") (name "Net-(IC6A-OUT)") (class "Default")
      (node (ref "C35") (pin "2") (pinfunction "2_2") (pintype "passive"))
      (node (ref "IC6") (pin "1") (pinfunction "OUT_1") (pintype "output"))
      (node (ref "R30") (pin "1") (pinfunction "1_1") (pintype "passive"))
      (node (ref "R42") (pin "2") (pinfunction "2_2") (pintype "passive"))
    )
    (net (code "58") (name "Net-(IC6B--IN)") (class "Default")
      (node (ref "C38") (pin "1") (pinfunction "1_1") (pintype "passive"))
      (node (ref "IC6") (pin "6") (pinfunction "-IN_6") (pintype "input"))
      (node (ref "R31") (pin "2") (pinfunction "2_2") (pintype "passive"))
      (node (ref "R34") (pin "1") (pinfunction "1_1") (pintype "passive"))
    )
    (net (code "59") (name "Net-(IC6B-OUT)") (class "Default")
      (node (ref "C38") (pin "2") (pinfunction "2_2") (pintype "passive"))
      (node (ref "IC6") (pin "7") (pinfunction "OUT_7") (pintype "output"))
      (node (ref "R31") (pin "1") (pinfunction "1_1") (pintype "passive"))
      (node (ref "R43") (pin "2") (pinfunction "2_2") (pintype "passive"))
    )
    (net (code "60") (name "Net-(J1-2)") (class "Default")
      (node (ref "J1") (pin "P2") (pinfunction "2_P2") (pintype "passive"))
      (node (ref "R32") (pin "2") (pinfunction "2_2") (pintype "passive"))
    )
    (net (code "61") (name "Net-(J1-3)") (class "Default")
      (node (ref "J1") (pin "P3") (pinfunction "3_P3") (pintype "passive"))
      (node (ref "R9") (pin "2") (pinfunction "2_2") (pintype "passive"))
    )
    (net (code "62") (name "Net-(J2-2)") (class "Default")
      (node (ref "J2") (pin "P2") (pinfunction "2_P2") (pintype "passive"))
      (node (ref "R35") (pin "2") (pinfunction "2_2") (pintype "passive"))
    )
    (net (code "63") (name "Net-(J2-3)") (class "Default")
      (node (ref "J2") (pin "P3") (pinfunction "3_P3") (pintype "passive"))
      (node (ref "R8") (pin "2") (pinfunction "2_2") (pintype "passive"))
    )
    (net (code "64") (name "Net-(J3-3)") (class "Default")
      (node (ref "J3") (pin "P3") (pinfunction "3_P3") (pintype "passive"))
      (node (ref "R17") (pin "2") (pinfunction "2_2") (pintype "passive"))
    )
    (net (code "65") (name "Net-(J4-3)") (class "Default")
      (node (ref "J4") (pin "P3") (pinfunction "3_P3") (pintype "passive"))
      (node (ref "R18") (pin "2") (pinfunction "2_2") (pintype "passive"))
    )
    (net (code "66") (name "Net-(J5-2)") (class "Default")
      (node (ref "J5") (pin "P2") (pinfunction "2_P2") (pintype "passive"))
      (node (ref "R40") (pin "1") (pinfunction "1_1") (pintype "passive"))
    )
    (net (code "67") (name "Net-(J5-3)") (class "Default")
      (node (ref "J5") (pin "P3") (pinfunction "3_P3") (pintype "passive"))
      (node (ref "R37") (pin "2") (pinfunction "2_2") (pintype "passive"))
    )
    (net (code "68") (name "Net-(J6-2)") (class "Default")
      (node (ref "J6") (pin "P2") (pinfunction "2_P2") (pintype "passive"))
      (node (ref "R41") (pin "1") (pinfunction "1_1") (pintype "passive"))
    )
    (net (code "69") (name "Net-(J6-3)") (class "Default")
      (node (ref "J6") (pin "P3") (pinfunction "3_P3") (pintype "passive"))
      (node (ref "R38") (pin "2") (pinfunction "2_2") (pintype "passive"))
    )
    (net (code "70") (name "Net-(J7-3)") (class "Default")
      (node (ref "J7") (pin "P3") (pinfunction "3_P3") (pintype "passive"))
      (node (ref "R42") (pin "1") (pinfunction "1_1") (pintype "passive"))
    )
    (net (code "71") (name "Net-(J8-3)") (class "Default")
      (node (ref "J8") (pin "P3") (pinfunction "3_P3") (pintype "passive"))
      (node (ref "R43") (pin "1") (pinfunction "1_1") (pintype "passive"))
    )
    (net (code "72") (name "Net-(LED1-PadBLU)") (class "Default")
      (node (ref "LED1") (pin "BLU") (pinfunction "BLU_BLU") (pintype "bidirectional"))
      (node (ref "R4") (pin "2") (pinfunction "2_2") (pintype "passive"))
    )
    (net (code "73") (name "Net-(LED1-PadGRN)") (class "Default")
      (node (ref "LED1") (pin "GRN") (pinfunction "GRN_GRN") (pintype "bidirectional"))
      (node (ref "R5") (pin "2") (pinfunction "2_2") (pintype "passive"))
    )
    (net (code "74") (name "Net-(LED1-PadRED)") (class "Default")
      (node (ref "LED1") (pin "RED") (pinfunction "RED_RED") (pintype "bidirectional"))
      (node (ref "R3") (pin "2") (pinfunction "2_2") (pintype "passive"))
    )
    (net (code "75") (name "Net-(LED2-GRN)") (class "Default")
      (node (ref "LED2") (pin "1") (pinfunction "GRN_1") (pintype "bidirectional"))
      (node (ref "R22") (pin "2") (pinfunction "2_2") (pintype "passive"))
    )
    (net (code "76") (name "Net-(LED2-RED)") (class "Default")
      (node (ref "LED2") (pin "3") (pinfunction "RED_3") (pintype "bidirectional"))
      (node (ref "R21") (pin "2") (pinfunction "2_2") (pintype "passive"))
    )
    (net (code "77") (name "PARAMETER_CV") (class "Default")
      (node (ref "C14") (pin "2") (pinfunction "2_2") (pintype "passive"))
      (node (ref "IC3") (pin "7") (pinfunction "OUT_7") (pintype "output"))
      (node (ref "IC4") (pin "17") (pinfunction "PA3/USART2_RX/ADC3/TIM2_CH4_17") (pintype "bidirectional"))
      (node (ref "R16") (pin "1") (pinfunction "1_1") (pintype "passive"))
    )
    (net (code "78") (name "PARAMETER_POT") (class "Default")
      (node (ref "C25") (pin "1") (pinfunction "1_1") (pintype "passive"))
      (node (ref "IC4") (pin "23") (pinfunction "PA7/SPI1_MOSI/ADC7/TIM3_CH2_23") (pintype "bidirectional"))
      (node (ref "R23") (pin "P$2") (pinfunction "S_P$2") (pintype "passive"))
    )
    (net (code "79") (name "RESET") (class "Default")
      (node (ref "IC4") (pin "7") (pinfunction "NRST_7") (pintype "bidirectional"))
      (node (ref "JP1") (pin "10") (pinfunction "10_10") (pintype "passive"))
      (node (ref "R2") (pin "1") (pinfunction "1_1") (pintype "passive"))
      (node (ref "SW1") (pin "B") (pinfunction "S_B") (pintype "passive"))
      (node (ref "SW1") (pin "B'") (pinfunction "S1_B'") (pintype "passive"))
    )
    (net (code "80") (name "RX") (class "Default")
      (node (ref "IC4") (pin "43") (pinfunction "PA10/USART1_RX/TIM1_CH3_43") (pintype "bidirectional"))
      (node (ref "JP2") (pin "4") (pinfunction "4_4") (pintype "passive"))
    )
    (net (code "81") (name "SW_CARRIER") (class "Default")
      (node (ref "IC4") (pin "27") (pinfunction "PB1/ADC9/TIM3_CH4_27") (pintype "bidirectional"))
      (node (ref "SW3") (pin "3") (pinfunction "3_3") (pintype "passive"))
      (node (ref "SW3") (pin "4") (pinfunction "4_4") (pintype "passive"))
    )
    (net (code "82") (name "TX") (class "Default")
      (node (ref "IC4") (pin "42") (pinfunction "PA9/USART1_TX/TIM1_CH2_42") (pintype "bidirectional"))
      (node (ref "JP2") (pin "5") (pinfunction "5_5") (pintype "passive"))
    )
    (net (code "83") (name "VBAT") (class "Default")
      (node (ref "IC4") (pin "1") (pinfunction "VBAT_1") (pintype "power_in"))
    )
    (net (code "84") (name "VCC") (class "Default")
      (node (ref "C1") (pin "+") (pinfunction "+_+") (pintype "passive"))
      (node (ref "C34") (pin "1") (pinfunction "1_1") (pintype "passive"))
      (node (ref "IC6") (pin "8") (pinfunction "V+_8") (pintype "power_in"))
      (node (ref "L1") (pin "1") (pinfunction "1_1") (pintype "passive"))
      (node (ref "R1") (pin "2") (pinfunction "2_2") (pintype "passive"))
    )
    (net (code "85") (name "VEE") (class "Default")
      (node (ref "C3") (pin "-") (pinfunction "-_-") (pintype "passive"))
      (node (ref "C40") (pin "2") (pinfunction "2_2") (pintype "passive"))
      (node (ref "IC6") (pin "4") (pinfunction "V-_4") (pintype "power_in"))
      (node (ref "L3") (pin "1") (pinfunction "1_1") (pintype "passive"))
      (node (ref "R6") (pin "1") (pinfunction "1_1") (pintype "passive"))
    )
    (net (code "86") (name "unconnected-(IC4-PA8{slash}USART1_CK{slash}TIM1_CH1{slash}MCO-Pad41)") (class "Default")
      (node (ref "IC4") (pin "41") (pinfunction "PA8/USART1_CK/TIM1_CH1/MCO_41") (pintype "bidirectional"))
    )
    (net (code "87") (name "unconnected-(IC4-PA11{slash}USART1_CTS{slash}CANRX{slash}USBDM{slash}TIM1_CH4-Pad44)") (class "Default")
      (node (ref "IC4") (pin "44") (pinfunction "PA11/USART1_CTS/CANRX/USBDM/TIM1_CH4_44") (pintype "bidirectional"))
    )
    (net (code "88") (name "unconnected-(IC4-PA12{slash}USART1_RTS{slash}CANTX{slash}USBDP{slash}TIM1_ETR-Pad45)") (class "Default")
      (node (ref "IC4") (pin "45") (pinfunction "PA12/USART1_RTS/CANTX/USBDP/TIM1_ETR_45") (pintype "bidirectional"))
    )
    (net (code "89") (name "unconnected-(IC4-PC0{slash}ADC10-Pad8)") (class "Default")
      (node (ref "IC4") (pin "8") (pinfunction "PC0/ADC10_8") (pintype "bidirectional"))
    )
    (net (code "90") (name "unconnected-(IC4-PC1{slash}ADC11-Pad9)") (class "Default")
      (node (ref "IC4") (pin "9") (pinfunction "PC1/ADC11_9") (pintype "bidirectional"))
    )
    (net (code "91") (name "unconnected-(IC4-PC2{slash}SPI2_MISO{slash}ADC12-Pad10)") (class "Default")
      (node (ref "IC4") (pin "10") (pinfunction "PC2/SPI2_MISO/ADC12_10") (pintype "bidirectional"))
    )
    (net (code "92") (name "unconnected-(IC4-PC3{slash}SPI2_MOSI{slash}I2S2_SD{slash}ADC13-Pad11)") (class "Default")
      (node (ref "IC4") (pin "11") (pinfunction "PC3/SPI2_MOSI/I2S2_SD/ADC13_11") (pintype "bidirectional"))
    )
    (net (code "93") (name "unconnected-(IC4-PC6{slash}I2S2_MCK-Pad37)") (class "Default")
      (node (ref "IC4") (pin "37") (pinfunction "PC6/I2S2_MCK_37") (pintype "bidirectional"))
    )
    (net (code "94") (name "unconnected-(IC4-PC7{slash}I2S3_MCK-Pad38)") (class "Default")
      (node (ref "IC4") (pin "38") (pinfunction "PC7/I2S3_MCK_38") (pintype "bidirectional"))
    )
    (net (code "95") (name "unconnected-(IC4-PC9{slash}I2S2_CKIN{slash}I2S3_CKIN-Pad40)") (class "Default")
      (node (ref "IC4") (pin "40") (pinfunction "PC9/I2S2_CKIN/I2S3_CKIN_40") (pintype "bidirectional"))
    )
    (net (code "96") (name "unconnected-(IC4-PC10{slash}SPI3_SCK{slash}I2S3_SCK{slash}UART4_TX-Pad51)") (class "Default")
      (node (ref "IC4") (pin "51") (pinfunction "PC10/SPI3_SCK/I2S3_SCK/UART4_TX_51") (pintype "bidirectional"))
    )
    (net (code "97") (name "unconnected-(IC4-PC12{slash}UART5_TX{slash}I2S3_SD{slash}USART3_CK-Pad53)") (class "Default")
      (node (ref "IC4") (pin "53") (pinfunction "PC12/UART5_TX/I2S3_SD/USART3_CK_53") (pintype "bidirectional"))
    )
    (net (code "98") (name "unconnected-(IC4-PC13-TAMPER-RTC-Pad2)") (class "Default")
      (node (ref "IC4") (pin "2") (pinfunction "PC13-TAMPER-RTC_2") (pintype "bidirectional"))
    )
    (net (code "99") (name "unconnected-(IC4-PC14{slash}OSC32_IN-Pad3)") (class "Default")
      (node (ref "IC4") (pin "3") (pinfunction "PC14/OSC32_IN_3") (pintype "bidirectional"))
    )
    (net (code "100") (name "unconnected-(IC4-PC15{slash}OSC_OUT-Pad4)") (class "Default")
      (node (ref "IC4") (pin "4") (pinfunction "PC15/OSC_OUT_4") (pintype "bidirectional"))
    )
    (net (code "101") (name "unconnected-(IC4-PD2{slash}TIM3-ETR-Pad54)") (class "Default")
      (node (ref "IC4") (pin "54") (pinfunction "PD2/TIM3-ETR_54") (pintype "bidirectional"))
    )
    (net (code "102") (name "unconnected-(IC5-CLKOUT-Pad2)") (class "Default")
      (node (ref "IC5") (pin "2") (pinfunction "CLKOUT_2") (pintype "bidirectional"))
    )
    (net (code "103") (name "unconnected-(IC5-LHPOUT-Pad9)") (class "Default")
      (node (ref "IC5") (pin "9") (pinfunction "LHPOUT_9") (pintype "bidirectional"))
    )
    (net (code "104") (name "unconnected-(IC5-MICBIAS-Pad17)") (class "Default")
      (node (ref "IC5") (pin "17") (pinfunction "MICBIAS_17") (pintype "bidirectional"))
    )
    (net (code "105") (name "unconnected-(IC5-MICIN-Pad18)") (class "Default")
      (node (ref "IC5") (pin "18") (pinfunction "MICIN_18") (pintype "bidirectional"))
    )
    (net (code "106") (name "unconnected-(IC5-RHPOUT-Pad10)") (class "Default")
      (node (ref "IC5") (pin "10") (pinfunction "RHPOUT_10") (pintype "bidirectional"))
    )
    (net (code "107") (name "unconnected-(J3-2-PadP2)") (class "Default")
      (node (ref "J3") (pin "P2") (pinfunction "2_P2") (pintype "passive"))
    )
    (net (code "108") (name "unconnected-(J4-2-PadP2)") (class "Default")
      (node (ref "J4") (pin "P2") (pinfunction "2_P2") (pintype "passive"))
    )
    (net (code "109") (name "unconnected-(J7-2-PadP2)") (class "Default")
      (node (ref "J7") (pin "P2") (pinfunction "2_P2") (pintype "passive"))
    )
    (net (code "110") (name "unconnected-(J8-2-PadP2)") (class "Default")
      (node (ref "J8") (pin "P2") (pinfunction "2_P2") (pintype "passive"))
    )
    (net (code "111") (name "unconnected-(JP1-Pad7)") (class "Default")
      (node (ref "JP1") (pin "7") (pinfunction "7_7") (pintype "passive"))
    )
    (net (code "112") (name "unconnected-(JP2-Pad2)") (class "Default")
      (node (ref "JP2") (pin "2") (pinfunction "2_2") (pintype "passive"))
    )
    (net (code "113") (name "unconnected-(JP2-Pad3)") (class "Default")
      (node (ref "JP2") (pin "3") (pinfunction "3_3") (pintype "passive"))
    )
    (net (code "114") (name "unconnected-(JP2-Pad6)") (class "Default")
      (node (ref "JP2") (pin "6") (pinfunction "6_6") (pintype "passive"))
    )
  )
)
